# CTR-Charging-Base-Rev-B-Power.net
KiCad netlist of a schematic drawn in Altium Designer
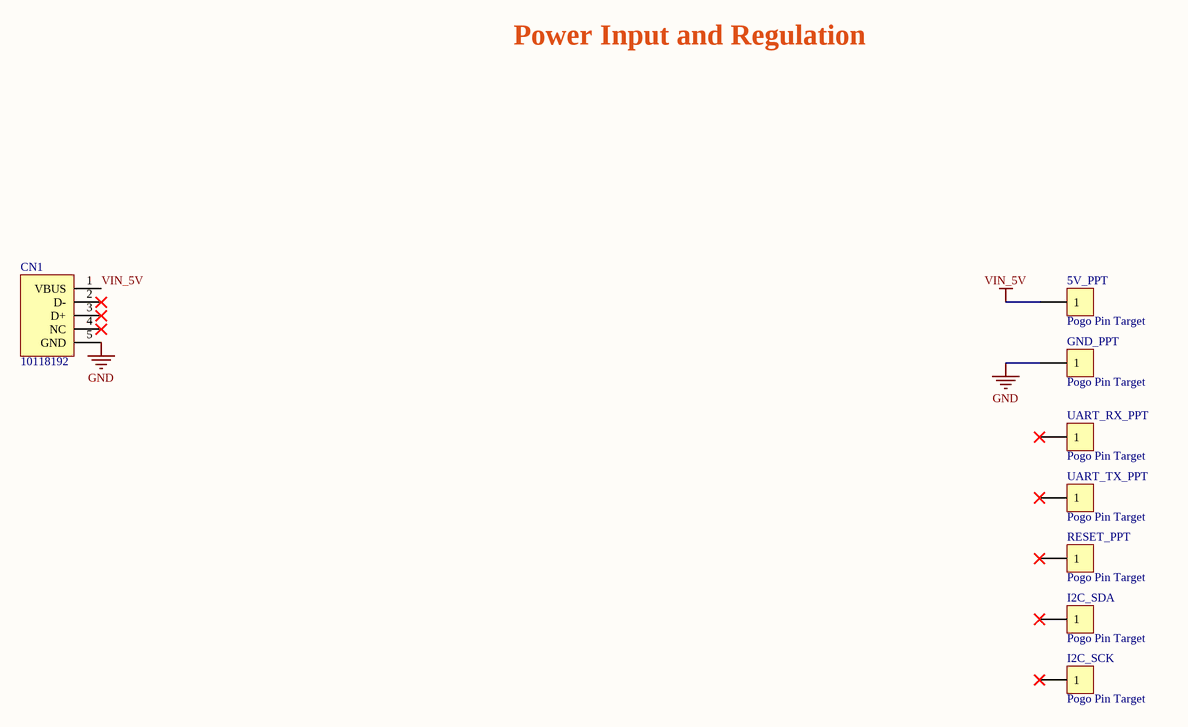
[diagram p0: CTR-Charging-Base-Rev-B-Power.SchDoc]

(export (version "E")
  (design (tool "Eeschema 10.0.6"))
  (components
    (comp (ref "5V_PPT")
      (value "Pogo Pin Target")
      (footprint "POGO_PIN")
      (fields
        (field (name "MANUFACTURER") "Mill-Max Manufacturing Corp.")
        (field (name "MANUFACTURER PART NUMBER") "1949-0-00-15-00-00-03-0")
      )
      (libsource (lib "OLogic-Connectors") (part "0850-0-15-20-83-14-11-0"))
    )
    (comp (ref "CN1")
      (value "10118192")
      (footprint "USB-MICRO-B")
      (description "Micro-USB RA Type B")
      (libsource (lib "OLogic-Connectors") (part "Micro-USB-B"))
    )
    (comp (ref "GND_PPT")
      (value "Pogo Pin Target")
      (footprint "POGO_PIN")
      (fields
        (field (name "MANUFACTURER") "Mill-Max Manufacturing Corp.")
        (field (name "MANUFACTURER PART NUMBER") "1949-0-00-15-00-00-03-0")
      )
      (libsource (lib "OLogic-Connectors") (part "0850-0-15-20-83-14-11-0"))
    )
    (comp (ref "I2C_SCK")
      (value "Pogo Pin Target")
      (footprint "POGO_PIN")
      (fields
        (field (name "MANUFACTURER") "Mill-Max Manufacturing Corp.")
        (field (name "MANUFACTURER PART NUMBER") "1949-0-00-15-00-00-03-0")
      )
      (libsource (lib "OLogic-Connectors") (part "0850-0-15-20-83-14-11-0"))
    )
    (comp (ref "I2C_SDA")
      (value "Pogo Pin Target")
      (footprint "POGO_PIN")
      (fields
        (field (name "MANUFACTURER") "Mill-Max Manufacturing Corp.")
        (field (name "MANUFACTURER PART NUMBER") "1949-0-00-15-00-00-03-0")
      )
      (libsource (lib "OLogic-Connectors") (part "0850-0-15-20-83-14-11-0"))
    )
    (comp (ref "RESET_PPT")
      (value "Pogo Pin Target")
      (footprint "POGO_PIN")
      (fields
        (field (name "MANUFACTURER") "Mill-Max Manufacturing Corp.")
        (field (name "MANUFACTURER PART NUMBER") "1949-0-00-15-00-00-03-0")
      )
      (libsource (lib "OLogic-Connectors") (part "0850-0-15-20-83-14-11-0"))
    )
    (comp (ref "UART_RX_PPT")
      (value "Pogo Pin Target")
      (footprint "POGO_PIN")
      (fields
        (field (name "MANUFACTURER") "Mill-Max Manufacturing Corp.")
        (field (name "MANUFACTURER PART NUMBER") "1949-0-00-15-00-00-03-0")
      )
      (libsource (lib "OLogic-Connectors") (part "0850-0-15-20-83-14-11-0"))
    )
    (comp (ref "UART_TX_PPT")
      (value "Pogo Pin Target")
      (footprint "POGO_PIN")
      (fields
        (field (name "MANUFACTURER") "Mill-Max Manufacturing Corp.")
        (field (name "MANUFACTURER PART NUMBER") "1949-0-00-15-00-00-03-0")
      )
      (libsource (lib "OLogic-Connectors") (part "0850-0-15-20-83-14-11-0"))
    )
  )
  (nets
    (net (code "1") (name "GND") (class "Default")
      (node (ref "CN1") (pin "5") (pinfunction "GND_5") (pintype "power_in"))
      (node (ref "GND_PPT") (pin "1") (pinfunction "1_1") (pintype "passive"))
    )
    (net (code "2") (name "VIN_5V") (class "Default")
      (node (ref "5V_PPT") (pin "1") (pinfunction "1_1") (pintype "passive"))
      (node (ref "CN1") (pin "1") (pinfunction "VBUS_1") (pintype "power_in"))
    )
    (net (code "3") (name "unconnected-(CN1-D+-Pad3)") (class "Default")
      (node (ref "CN1") (pin "3") (pinfunction "D+_3") (pintype "passive+no_connect"))
    )
    (net (code "4") (name "unconnected-(CN1-D--Pad2)") (class "Default")
      (node (ref "CN1") (pin "2") (pinfunction "D-_2") (pintype "passive+no_connect"))
    )
    (net (code "5") (name "unconnected-(CN1-NC-Pad4)") (class "Default")
      (node (ref "CN1") (pin "4") (pinfunction "NC_4") (pintype "passive+no_connect"))
    )
    (net (code "6") (name "unconnected-(I2C_SCK-Pad1)") (class "Default")
      (node (ref "I2C_SCK") (pin "1") (pinfunction "1_1") (pintype "passive+no_connect"))
    )
    (net (code "7") (name "unconnected-(I2C_SDA-Pad1)") (class "Default")
      (node (ref "I2C_SDA") (pin "1") (pinfunction "1_1") (pintype "passive+no_connect"))
    )
    (net (code "8") (name "unconnected-(RESET_PPT-Pad1)") (class "Default")
      (node (ref "RESET_PPT") (pin "1") (pinfunction "1_1") (pintype "passive+no_connect"))
    )
    (net (code "9") (name "unconnected-(UART_RX_PPT-Pad1)") (class "Default")
      (node (ref "UART_RX_PPT") (pin "1") (pinfunction "1_1") (pintype "passive+no_connect"))
    )
    (net (code "10") (name "unconnected-(UART_TX_PPT-Pad1)") (class "Default")
      (node (ref "UART_TX_PPT") (pin "1") (pinfunction "1_1") (pintype "passive+no_connect"))
    )
  )
)
